# AC_SUPPLY.net
KiCad netlist of a schematic drawn in Altium Designer
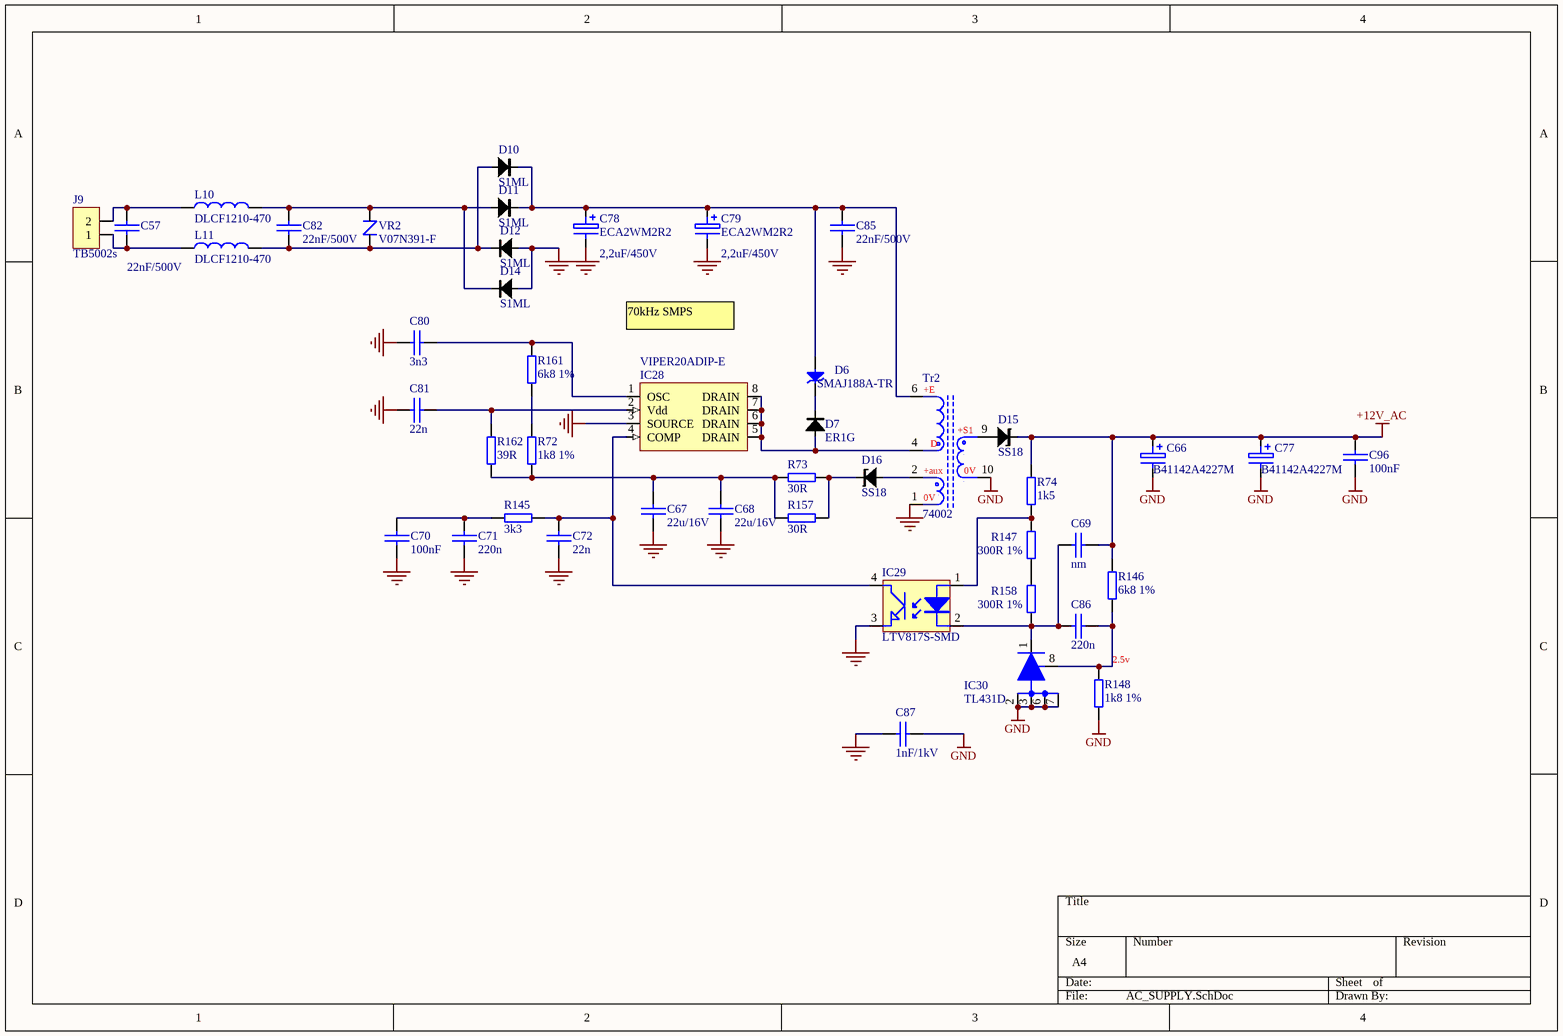
[diagram p0: AC_SUPPLY.SchDoc]

(export (version "E")
  (design (tool "Eeschema 10.0.6"))
  (components
    (comp (ref "C57")
      (value "22nF/500V")
      (footprint "1206C")
      (description "Capacitor SMD")
      (libsource (lib "LIBRARY_SCH") (part "CAP_SMD_1206"))
    )
    (comp (ref "C66")
      (value "B41142A4227M")
      (footprint "CAP_SMT_EL_5mm_C")
      (description "Electrolytic Capacitor")
      (libsource (lib "LIBRARY_SCH") (part "CAP_ELECTRO_SMD_C"))
    )
    (comp (ref "C67")
      (value "22u/16V")
      (footprint "1206C")
      (description "Capacitor SMD")
      (libsource (lib "LIBRARY_SCH") (part "CAP_SMD_0805"))
    )
    (comp (ref "C68")
      (value "22u/16V")
      (footprint "1206C")
      (description "Capacitor SMD")
      (libsource (lib "LIBRARY_SCH") (part "CAP_SMD_0805"))
    )
    (comp (ref "C69")
      (value "nm")
      (footprint "0402C")
      (description "Capacitor SMD")
      (libsource (lib "LIBRARY_SCH") (part "CAP_SMD_0402"))
    )
    (comp (ref "C70")
      (value "100nF")
      (footprint "0402C")
      (description "Capacitor SMD")
      (libsource (lib "LIBRARY_SCH") (part "CAP_SMD_0402"))
    )
    (comp (ref "C71")
      (value "220n")
      (footprint "0603C")
      (description "Capacitor SMD")
      (libsource (lib "LIBRARY_SCH") (part "CAP_SMD_0603"))
    )
    (comp (ref "C72")
      (value "22n")
      (footprint "0603C")
      (description "Capacitor SMD")
      (libsource (lib "LIBRARY_SCH") (part "CAP_SMD_0603"))
    )
    (comp (ref "C77")
      (value "B41142A4227M")
      (footprint "CAP_SMT_EL_5mm_C")
      (description "Electrolytic Capacitor")
      (libsource (lib "LIBRARY_SCH") (part "CAP_ELECTRO_SMD_C"))
    )
    (comp (ref "C78")
      (value "ECA2WM2R2")
      (footprint "RB.2/.4")
      (description "Electrolytic Capacitor")
      (fields (field (name "ALTIUM_VALUE") "2,2uF/450V"))
      (libsource (lib "LIBRARY_SCH") (part "CAP_ELECTRO_10mm"))
    )
    (comp (ref "C79")
      (value "ECA2WM2R2")
      (footprint "RB.2/.4")
      (description "Electrolytic Capacitor")
      (fields (field (name "ALTIUM_VALUE") "2,2uF/450V"))
      (libsource (lib "LIBRARY_SCH") (part "CAP_ELECTRO_10mm"))
    )
    (comp (ref "C80")
      (value "3n3")
      (footprint "0603C")
      (description "Capacitor SMD")
      (libsource (lib "LIBRARY_SCH") (part "CAP_SMD_0603"))
    )
    (comp (ref "C81")
      (value "22n")
      (footprint "0603C")
      (description "Capacitor SMD")
      (libsource (lib "LIBRARY_SCH") (part "CAP_SMD_0603"))
    )
    (comp (ref "C82")
      (value "22nF/500V")
      (footprint "1206C")
      (description "Capacitor SMD")
      (libsource (lib "LIBRARY_SCH") (part "CAP_SMD_1206"))
    )
    (comp (ref "C85")
      (value "22nF/500V")
      (footprint "1206C")
      (description "Capacitor SMD")
      (libsource (lib "LIBRARY_SCH") (part "CAP_SMD_1206"))
    )
    (comp (ref "C86")
      (value "220n")
      (footprint "0603C")
      (description "Capacitor SMD")
      (libsource (lib "LIBRARY_SCH") (part "CAP_SMD_0603"))
    )
    (comp (ref "C87")
      (value "1nF/1kV")
      (footprint "1206C")
      (description "Capacitor SMD")
      (libsource (lib "LIBRARY_SCH") (part "CAP_SMD_1206"))
    )
    (comp (ref "C96")
      (value "100nF")
      (footprint "0402C")
      (description "Capacitor SMD")
      (libsource (lib "LIBRARY_SCH") (part "CAP_SMD_0402"))
    )
    (comp (ref "D6")
      (value "SMAJ188A-TR")
      (footprint "DO-214AA/SMB")
      (description "TVS, 200V")
      (fields
        (field (name "PART NUMBER") "P6KE200A")
        (field (name "VOLTAGE") "200V")
        (field (name "AUTHOR") "CERN DEM JMW")
      )
      (libsource (lib "LIBRARY_SCH") (part "D_TVS_600W"))
    )
    (comp (ref "D7")
      (value "ER1G")
      (footprint "DO-214AA/SMB")
      (description "1A, 400V, 35ns")
      (libsource (lib "LIBRARY_SCH") (part "D_ER1G"))
    )
    (comp (ref "D10")
      (value "S1ML")
      (footprint "SOD-123")
      (description "1A, 1000V, 1.8us")
      (libsource (lib "LIBRARY_SCH") (part "D_S1ML"))
    )
    (comp (ref "D11")
      (value "S1ML")
      (footprint "SOD-123")
      (description "1A, 1000V, 1.8us")
      (libsource (lib "LIBRARY_SCH") (part "D_S1ML"))
    )
    (comp (ref "D12")
      (value "S1ML")
      (footprint "SOD-123")
      (description "1A, 1000V, 1.8us")
      (libsource (lib "") (part "D_S1ML_1"))
    )
    (comp (ref "D14")
      (value "S1ML")
      (footprint "SOD-123")
      (description "1A, 1000V, 1.8us")
      (libsource (lib "") (part "D_S1ML_1"))
    )
    (comp (ref "D15")
      (value "SS18")
      (footprint "DO-214AC/SMA")
      (description "shottky diode (Maritex)")
      (libsource (lib "LIBRARY_SCH") (part "D_shottky_SS14_18"))
    )
    (comp (ref "D16")
      (value "SS18")
      (footprint "DO-214AC/SMA")
      (description "shottky diode (Maritex)")
      (libsource (lib "") (part "D_shottky_SS14_18_1"))
    )
    (comp (ref "IC28")
      (value "VIPER20ADIP-E")
      (footprint "DIP-8")
      (description "20W SMPS PRIMARY I.C.")
      (libsource (lib "LIBRARY_SCH") (part "PWM_VIPER20"))
    )
    (comp (ref "IC29")
      (value "LTV817S-SMD")
      (footprint "SOP_4")
      (description "transoptor")
      (libsource (lib "LIBRARY_SCH") (part "OPTO-LTV817S"))
    )
    (comp (ref "IC30")
      (value "TL431D")
      (footprint "SO-8")
      (description "Voltage reference")
      (libsource (lib "LIBRARY_SCH") (part "REF_TL431_SO8"))
    )
    (comp (ref "J9")
      (value "TB5002s")
      (footprint "tb5002s")
      (description "Terminal Block")
      (libsource (lib "LIBRARY_SCH") (part "CON_TB2"))
    )
    (comp (ref "L10")
      (value "DLCF1210-470")
      (footprint "DLCF1210")
      (description "Inductor (maritex)")
      (libsource (lib "LIBRARY_SCH") (part "L_CHOKE_1210"))
    )
    (comp (ref "L11")
      (value "DLCF1210-470")
      (footprint "DLCF1210")
      (description "Inductor (maritex)")
      (libsource (lib "LIBRARY_SCH") (part "L_CHOKE_1210"))
    )
    (comp (ref "R72")
      (value "1k8 1%")
      (footprint "0603R")
      (description "SMD Resistor")
      (libsource (lib "LIBRARY_SCH") (part "RES_0603"))
    )
    (comp (ref "R73")
      (value "30R")
      (footprint "0603R")
      (description "SMD Resistor")
      (libsource (lib "") (part "RES_0603_1"))
    )
    (comp (ref "R74")
      (value "1k5")
      (footprint "0805R")
      (description "SMD Resistor")
      (libsource (lib "LIBRARY_SCH") (part "RES_0805"))
    )
    (comp (ref "R145")
      (value "3k3")
      (footprint "0603R")
      (description "SMD Resistor")
      (libsource (lib "LIBRARY_SCH") (part "RES_0603"))
    )
    (comp (ref "R146")
      (value "6k8 1%")
      (footprint "0603R")
      (description "SMD Resistor")
      (libsource (lib "LIBRARY_SCH") (part "RES_0603"))
    )
    (comp (ref "R147")
      (value "300R 1%")
      (footprint "0603R")
      (description "SMD Resistor")
      (libsource (lib "LIBRARY_SCH") (part "RES_0603"))
    )
    (comp (ref "R148")
      (value "1k8 1%")
      (footprint "0603R")
      (description "SMD Resistor")
      (libsource (lib "LIBRARY_SCH") (part "RES_0603"))
    )
    (comp (ref "R157")
      (value "30R")
      (footprint "0603R")
      (description "SMD Resistor")
      (libsource (lib "") (part "RES_0603_1"))
    )
    (comp (ref "R158")
      (value "300R 1%")
      (footprint "0603R")
      (description "SMD Resistor")
      (libsource (lib "LIBRARY_SCH") (part "RES_0603"))
    )
    (comp (ref "R161")
      (value "6k8 1%")
      (footprint "0603R")
      (description "SMD Resistor")
      (libsource (lib "LIBRARY_SCH") (part "RES_0603"))
    )
    (comp (ref "R162")
      (value "39R")
      (footprint "0805R")
      (description "SMD Resistor")
      (libsource (lib "LIBRARY_SCH") (part "RES_0805"))
    )
    (comp (ref "Tr2")
      (value "74002")
      (footprint "Tr_74002_MYRRA")
      (description "6W 12V flyback transformer (MYRRA)")
      (libsource (lib "LIBRARY_SCH") (part "Tr_74002"))
    )
    (comp (ref "VR2")
      (value "V07N391-F")
      (footprint "Varistor_V07")
      (description "varistor 7mm (Maritex)")
      (libsource (lib "LIBRARY_SCH") (part "Varistor V07N"))
    )
  )
  (nets
    (net (code "1") (name "+12V_AC") (class "Default")
      (node (ref "C66") (pin "1") (pinfunction "1_1") (pintype "passive"))
      (node (ref "C69") (pin "2") (pinfunction "2_2") (pintype "passive"))
      (node (ref "C77") (pin "1") (pinfunction "1_1") (pintype "passive"))
      (node (ref "C96") (pin "1") (pinfunction "1_1") (pintype "passive"))
      (node (ref "D15") (pin "K") (pinfunction "K_K") (pintype "passive"))
      (node (ref "R146") (pin "1") (pinfunction "1_1") (pintype "passive"))
      (node (ref "R74") (pin "1") (pinfunction "1_1") (pintype "passive"))
    )
    (net (code "2") (name "GND") (class "Default")
      (node (ref "C66") (pin "2") (pinfunction "2_2") (pintype "passive"))
      (node (ref "C77") (pin "2") (pinfunction "2_2") (pintype "passive"))
      (node (ref "C87") (pin "2") (pinfunction "2_2") (pintype "passive"))
      (node (ref "C96") (pin "2") (pinfunction "2_2") (pintype "passive"))
      (node (ref "IC30") (pin "2") (pinfunction "A_2") (pintype "passive"))
      (node (ref "IC30") (pin "3") (pinfunction "A_3") (pintype "passive"))
      (node (ref "IC30") (pin "6") (pinfunction "K_6") (pintype "passive"))
      (node (ref "IC30") (pin "7") (pinfunction "A_7") (pintype "passive"))
      (node (ref "R148") (pin "2") (pinfunction "2_2") (pintype "passive"))
      (node (ref "Tr2") (pin "10") (pinfunction "10_10") (pintype "passive"))
    )
    (net (code "3") (name "HGND") (class "Default")
      (node (ref "C67") (pin "2") (pinfunction "2_2") (pintype "passive"))
      (node (ref "C68") (pin "2") (pinfunction "2_2") (pintype "passive"))
      (node (ref "C70") (pin "2") (pinfunction "2_2") (pintype "passive"))
      (node (ref "C71") (pin "2") (pinfunction "2_2") (pintype "passive"))
      (node (ref "C72") (pin "2") (pinfunction "2_2") (pintype "passive"))
      (node (ref "C78") (pin "2") (pinfunction "2_2") (pintype "passive"))
      (node (ref "C79") (pin "2") (pinfunction "2_2") (pintype "passive"))
      (node (ref "C80") (pin "1") (pinfunction "1_1") (pintype "passive"))
      (node (ref "C81") (pin "1") (pinfunction "1_1") (pintype "passive"))
      (node (ref "C85") (pin "1") (pinfunction "1_1") (pintype "passive"))
      (node (ref "C87") (pin "1") (pinfunction "1_1") (pintype "passive"))
      (node (ref "D12") (pin "A") (pinfunction "A_A") (pintype "passive"))
      (node (ref "D14") (pin "A") (pinfunction "A_A") (pintype "passive"))
      (node (ref "IC28") (pin "3") (pinfunction "SOURCE_3") (pintype "passive"))
      (node (ref "IC29") (pin "3") (pinfunction "C_3") (pintype "passive"))
      (node (ref "Tr2") (pin "1") (pintype "passive"))
    )
    (net (code "4") (name "Net-(C57-Pad1)") (class "Default")
      (node (ref "C57") (pin "1") (pinfunction "1_1") (pintype "passive"))
      (node (ref "J9") (pin "1") (pinfunction "1_1") (pintype "passive"))
      (node (ref "L11") (pin "1") (pinfunction "1_1") (pintype "passive"))
    )
    (net (code "5") (name "Net-(C57-Pad2)") (class "Default")
      (node (ref "C57") (pin "2") (pinfunction "2_2") (pintype "passive"))
      (node (ref "J9") (pin "2") (pinfunction "2_2") (pintype "passive"))
      (node (ref "L10") (pin "1") (pinfunction "1_1") (pintype "passive"))
    )
    (net (code "6") (name "Net-(C67-Pad1)") (class "Default")
      (node (ref "C67") (pin "1") (pinfunction "1_1") (pintype "passive"))
      (node (ref "C68") (pin "1") (pinfunction "1_1") (pintype "passive"))
      (node (ref "R157") (pin "1") (pinfunction "1_1") (pintype "passive"))
      (node (ref "R162") (pin "2") (pinfunction "2_2") (pintype "passive"))
      (node (ref "R72") (pin "1") (pinfunction "1_1") (pintype "passive"))
      (node (ref "R73") (pin "1") (pinfunction "1_1") (pintype "passive"))
    )
    (net (code "7") (name "Net-(C70-Pad1)") (class "Default")
      (node (ref "C70") (pin "1") (pinfunction "1_1") (pintype "passive"))
      (node (ref "C71") (pin "1") (pinfunction "1_1") (pintype "passive"))
      (node (ref "R145") (pin "1") (pinfunction "1_1") (pintype "passive"))
    )
    (net (code "8") (name "Net-(C78-Pad1)") (class "Default")
      (node (ref "C78") (pin "1") (pinfunction "1_1") (pintype "passive"))
      (node (ref "C79") (pin "1") (pinfunction "1_1") (pintype "passive"))
      (node (ref "C85") (pin "2") (pinfunction "2_2") (pintype "passive"))
      (node (ref "D10") (pin "K") (pinfunction "K_K") (pintype "passive"))
      (node (ref "D11") (pin "K") (pinfunction "K_K") (pintype "passive"))
      (node (ref "D6") (pin "A") (pinfunction "A_A") (pintype "passive"))
      (node (ref "Tr2") (pin "6") (pintype "passive"))
    )
    (net (code "9") (name "Net-(C82-Pad1)") (class "Default")
      (node (ref "C82") (pin "1") (pinfunction "1_1") (pintype "passive"))
      (node (ref "D10") (pin "A") (pinfunction "A_A") (pintype "passive"))
      (node (ref "D12") (pin "K") (pinfunction "K_K") (pintype "passive"))
      (node (ref "L11") (pin "2") (pinfunction "2_2") (pintype "passive"))
      (node (ref "VR2") (pin "2") (pinfunction "2_2") (pintype "power_in"))
    )
    (net (code "10") (name "Net-(C82-Pad2)") (class "Default")
      (node (ref "C82") (pin "2") (pinfunction "2_2") (pintype "passive"))
      (node (ref "D11") (pin "A") (pinfunction "A_A") (pintype "passive"))
      (node (ref "D14") (pin "K") (pinfunction "K_K") (pintype "passive"))
      (node (ref "L10") (pin "2") (pinfunction "2_2") (pintype "passive"))
      (node (ref "VR2") (pin "1") (pinfunction "1_1") (pintype "power_in"))
    )
    (net (code "11") (name "Net-(D6-PadK)") (class "Default")
      (node (ref "D6") (pin "K") (pinfunction "K_K") (pintype "passive"))
      (node (ref "D7") (pin "K") (pinfunction "K_K") (pintype "passive"))
    )
    (net (code "12") (name "Net-(D7-PadA)") (class "Default")
      (node (ref "D7") (pin "A") (pinfunction "A_A") (pintype "passive"))
      (node (ref "IC28") (pin "5") (pinfunction "DRAIN_5") (pintype "open_collector"))
      (node (ref "IC28") (pin "6") (pinfunction "DRAIN_6") (pintype "open_collector"))
      (node (ref "IC28") (pin "7") (pinfunction "DRAIN_7") (pintype "open_collector"))
      (node (ref "IC28") (pin "8") (pinfunction "DRAIN_8") (pintype "open_collector"))
      (node (ref "Tr2") (pin "4") (pintype "passive"))
    )
    (net (code "13") (name "Net-(D15-PadA)") (class "Default")
      (node (ref "D15") (pin "A") (pinfunction "A_A") (pintype "passive"))
      (node (ref "Tr2") (pin "9") (pinfunction "9_9") (pintype "passive"))
    )
    (net (code "14") (name "Net-(D16-PadA)") (class "Default")
      (node (ref "D16") (pin "A") (pinfunction "A_A") (pintype "passive"))
      (node (ref "Tr2") (pin "2") (pintype "passive"))
    )
    (net (code "15") (name "Net-(D16-PadK)") (class "Default")
      (node (ref "D16") (pin "K") (pinfunction "K_K") (pintype "passive"))
      (node (ref "R157") (pin "2") (pinfunction "2_2") (pintype "passive"))
      (node (ref "R73") (pin "2") (pinfunction "2_2") (pintype "passive"))
    )
    (net (code "16") (name "Net-(IC28-COMP)") (class "Default")
      (node (ref "C72") (pin "1") (pinfunction "1_1") (pintype "passive"))
      (node (ref "IC28") (pin "4") (pinfunction "COMP_4") (pintype "input"))
      (node (ref "IC29") (pin "4") (pinfunction "E_4") (pintype "passive"))
      (node (ref "R145") (pin "2") (pinfunction "2_2") (pintype "passive"))
    )
    (net (code "17") (name "Net-(IC28-OSC)") (class "Default")
      (node (ref "C80") (pin "2") (pinfunction "2_2") (pintype "passive"))
      (node (ref "IC28") (pin "1") (pinfunction "OSC_1") (pintype "passive"))
      (node (ref "R161") (pin "1") (pinfunction "1_1") (pintype "passive"))
    )
    (net (code "18") (name "Net-(IC28-Vdd)") (class "Default")
      (node (ref "C81") (pin "2") (pinfunction "2_2") (pintype "passive"))
      (node (ref "IC28") (pin "2") (pinfunction "Vdd_2") (pintype "input"))
      (node (ref "R162") (pin "1") (pinfunction "1_1") (pintype "passive"))
    )
    (net (code "19") (name "Net-(IC29-A)") (class "Default")
      (node (ref "IC29") (pin "1") (pinfunction "A_1") (pintype "passive"))
      (node (ref "R147") (pin "1") (pinfunction "1_1") (pintype "passive"))
      (node (ref "R74") (pin "2") (pinfunction "2_2") (pintype "passive"))
    )
    (net (code "20") (name "Net-(IC29-K)") (class "Default")
      (node (ref "C69") (pin "1") (pinfunction "1_1") (pintype "passive"))
      (node (ref "C86") (pin "1") (pinfunction "1_1") (pintype "passive"))
      (node (ref "IC29") (pin "2") (pinfunction "K_2") (pintype "passive"))
      (node (ref "IC30") (pin "1") (pinfunction "I/O_1") (pintype "passive"))
      (node (ref "R158") (pin "2") (pinfunction "2_2") (pintype "passive"))
    )
    (net (code "21") (name "Net-(IC30-REF)") (class "Default")
      (node (ref "C86") (pin "2") (pinfunction "2_2") (pintype "passive"))
      (node (ref "IC30") (pin "8") (pinfunction "REF_8") (pintype "passive"))
      (node (ref "R146") (pin "2") (pinfunction "2_2") (pintype "passive"))
      (node (ref "R148") (pin "1") (pinfunction "1_1") (pintype "passive"))
    )
    (net (code "22") (name "Net-(R147-Pad2)") (class "Default")
      (node (ref "R147") (pin "2") (pinfunction "2_2") (pintype "passive"))
      (node (ref "R158") (pin "1") (pinfunction "1_1") (pintype "passive"))
    )
    (net (code "23") (name "Net-(R161-Pad2)") (class "Default")
      (node (ref "R161") (pin "2") (pinfunction "2_2") (pintype "passive"))
      (node (ref "R72") (pin "2") (pinfunction "2_2") (pintype "passive"))
    )
  )
)
